# design.net
KiCad netlist of a schematic drawn in Altium Designer
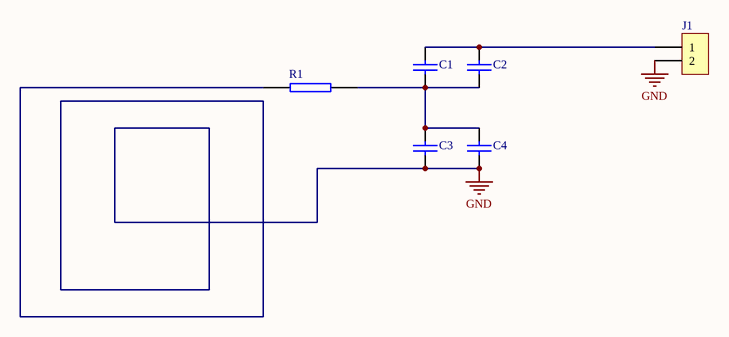
[diagram p0: 刷卡面板.SchDoc]

(export (version "E")
  (design (tool "Eeschema 10.0.6"))
  (components
    (comp (ref "C1")
      (value "CAP")
      (footprint "0603_C")
      (description "Capacitor")
      (libsource (lib "SCH") (part "CAP"))
    )
    (comp (ref "C2")
      (value "CAP")
      (footprint "0603_C")
      (description "Capacitor")
      (libsource (lib "SCH") (part "CAP"))
    )
    (comp (ref "C3")
      (value "CAP")
      (footprint "0603_C")
      (description "Capacitor")
      (libsource (lib "SCH") (part "CAP"))
    )
    (comp (ref "C4")
      (value "CAP")
      (footprint "0603_C")
      (description "Capacitor")
      (libsource (lib "SCH") (part "CAP"))
    )
    (comp (ref "J1")
      (value "CON2")
      (footprint "sip2")
      (description "Connector")
      (libsource (lib "SCH") (part "CON2"))
    )
    (comp (ref "R1") (value "RES2") (footprint "0603") (libsource (lib "SCH") (part "RES2")))
  )
  (nets
    (net (code "1") (name "GND") (class "Default")
      (node (ref "C3") (pin "2") (pinfunction "2_2") (pintype "passive"))
      (node (ref "C4") (pin "2") (pinfunction "2_2") (pintype "passive"))
      (node (ref "J1") (pin "2") (pinfunction "2_2") (pintype "passive"))
      (node (ref "R1") (pin "1") (pinfunction "1_1") (pintype "passive"))
    )
    (net (code "2") (name "Net-(C1-Pad1)") (class "Default")
      (node (ref "C1") (pin "1") (pinfunction "1_1") (pintype "passive"))
      (node (ref "C2") (pin "1") (pinfunction "1_1") (pintype "passive"))
      (node (ref "J1") (pin "1") (pinfunction "1_1") (pintype "passive"))
    )
    (net (code "3") (name "Net-(C1-Pad2)") (class "Default")
      (node (ref "C1") (pin "2") (pinfunction "2_2") (pintype "passive"))
      (node (ref "C2") (pin "2") (pinfunction "2_2") (pintype "passive"))
      (node (ref "C3") (pin "1") (pinfunction "1_1") (pintype "passive"))
      (node (ref "C4") (pin "1") (pinfunction "1_1") (pintype "passive"))
      (node (ref "R1") (pin "2") (pinfunction "2_2") (pintype "passive"))
    )
  )
)
